# gyro_pcb.net
KiCad netlist of a schematic drawn in EAGLE
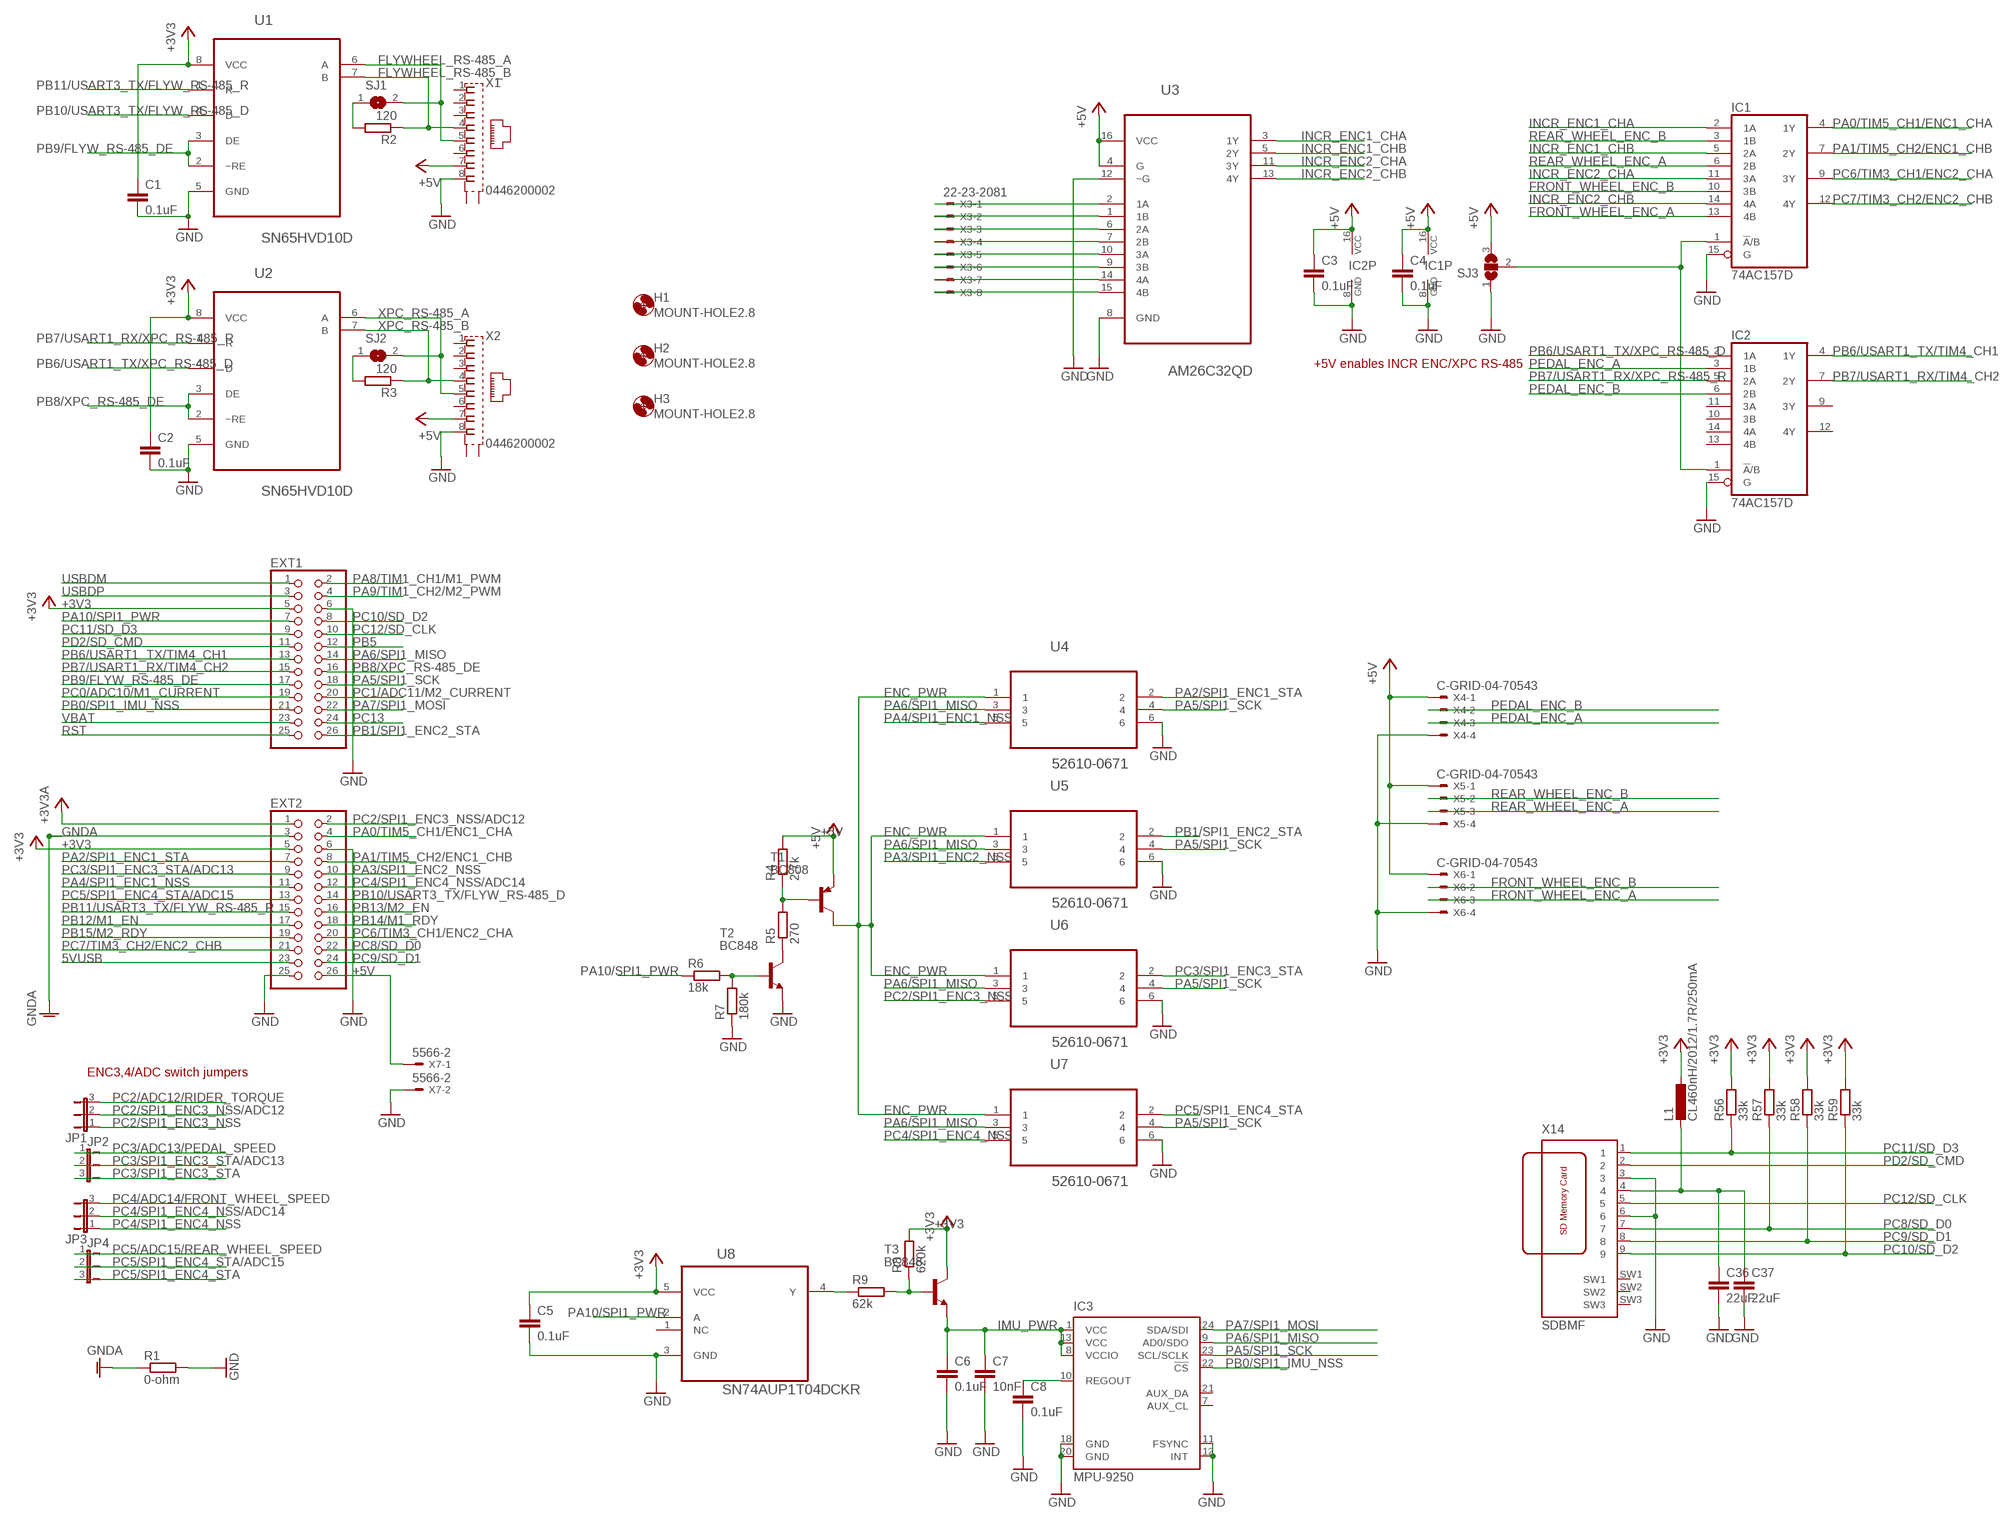
[diagram p0: schematic, sheet 1, part 1 of 2]
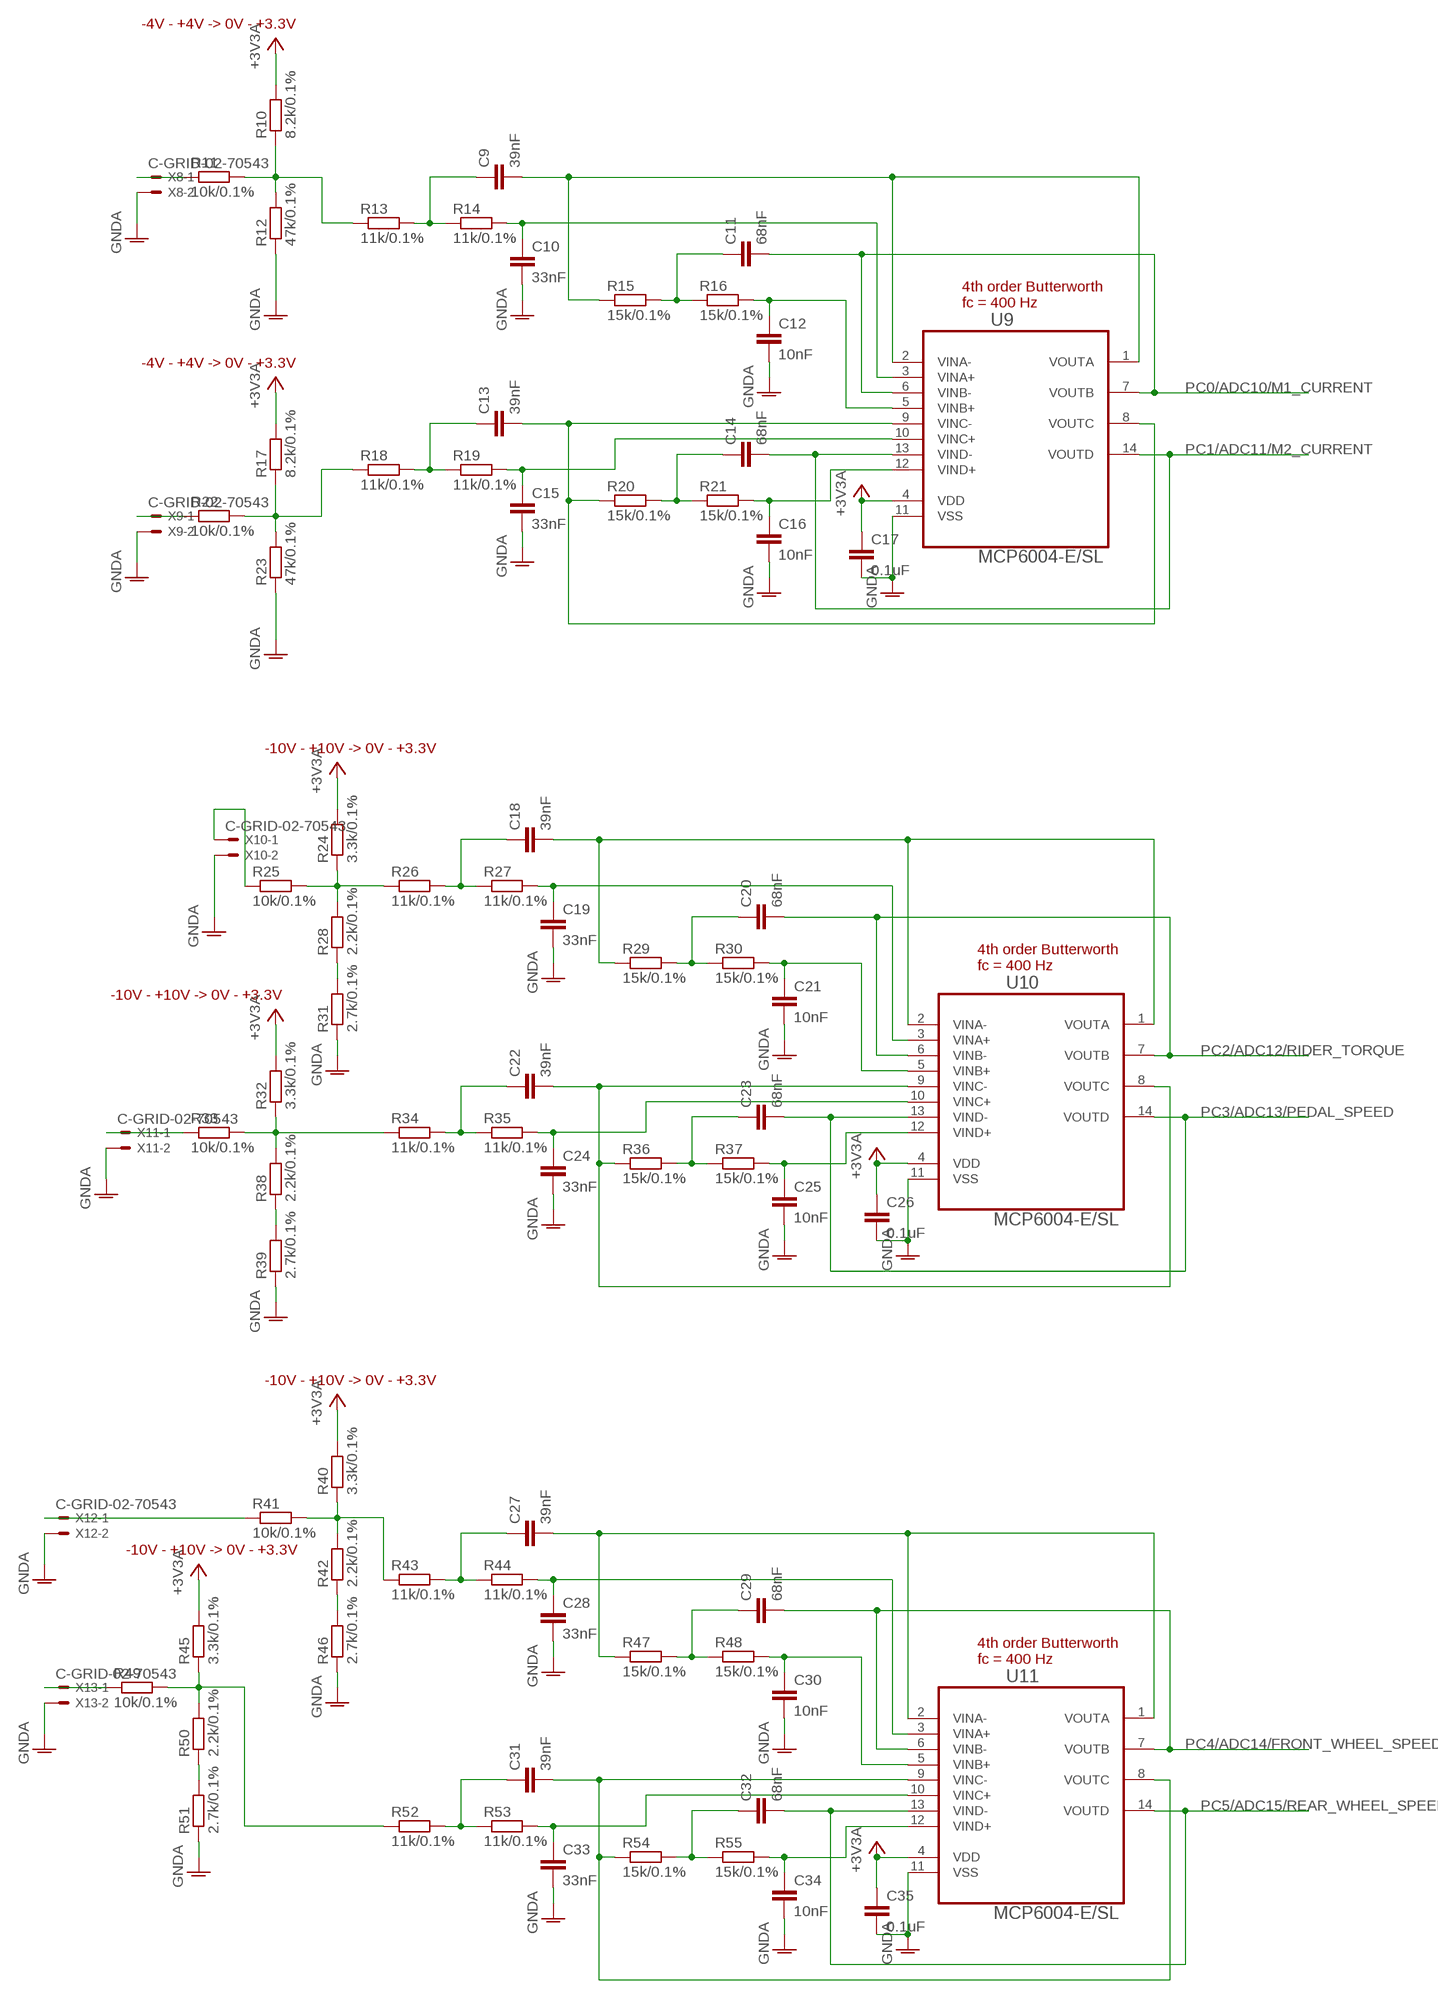
[diagram p1: schematic, sheet 1, part 2 of 2]

(export (version "E")
  (design (tool "Eeschema 10.0.6"))
  (components
    (comp (ref "C1")
      (value "0.1uF")
      (footprint "eagle-import:C0603")
      (libsource (lib "eagle-import") (part "C-EUC0603"))
    )
    (comp (ref "C2")
      (value "0.1uF")
      (footprint "eagle-import:C0603")
      (libsource (lib "eagle-import") (part "C-EUC0603"))
    )
    (comp (ref "C3")
      (value "0.1uF")
      (footprint "eagle-import:C0603")
      (libsource (lib "eagle-import") (part "C-EUC0603"))
    )
    (comp (ref "C4")
      (value "0.1uF")
      (footprint "eagle-import:C0603")
      (libsource (lib "eagle-import") (part "C-EUC0603"))
    )
    (comp (ref "C5")
      (value "0.1uF")
      (footprint "eagle-import:C0603")
      (libsource (lib "eagle-import") (part "C-EUC0603"))
    )
    (comp (ref "C6")
      (value "0.1uF")
      (footprint "eagle-import:C0603")
      (libsource (lib "eagle-import") (part "C-EUC0603"))
    )
    (comp (ref "C7")
      (value "10nF")
      (footprint "eagle-import:C0603")
      (libsource (lib "eagle-import") (part "C-EUC0603"))
    )
    (comp (ref "C8")
      (value "0.1uF")
      (footprint "eagle-import:C0603")
      (libsource (lib "eagle-import") (part "C-EUC0603"))
    )
    (comp (ref "C9")
      (value "39nF")
      (footprint "eagle-import:C0603")
      (libsource (lib "eagle-import") (part "C-EUC0603"))
    )
    (comp (ref "C10")
      (value "33nF")
      (footprint "eagle-import:C0603")
      (libsource (lib "eagle-import") (part "C-EUC0603"))
    )
    (comp (ref "C11")
      (value "68nF")
      (footprint "eagle-import:C0603")
      (libsource (lib "eagle-import") (part "C-EUC0603"))
    )
    (comp (ref "C12")
      (value "10nF")
      (footprint "eagle-import:C0603")
      (libsource (lib "eagle-import") (part "C-EUC0603"))
    )
    (comp (ref "C13")
      (value "39nF")
      (footprint "eagle-import:C0603")
      (libsource (lib "eagle-import") (part "C-EUC0603"))
    )
    (comp (ref "C14")
      (value "68nF")
      (footprint "eagle-import:C0603")
      (libsource (lib "eagle-import") (part "C-EUC0603"))
    )
    (comp (ref "C15")
      (value "33nF")
      (footprint "eagle-import:C0603")
      (libsource (lib "eagle-import") (part "C-EUC0603"))
    )
    (comp (ref "C16")
      (value "10nF")
      (footprint "eagle-import:C0603")
      (libsource (lib "eagle-import") (part "C-EUC0603"))
    )
    (comp (ref "C17")
      (value "0.1uF")
      (footprint "eagle-import:C0603")
      (libsource (lib "eagle-import") (part "C-EUC0603"))
    )
    (comp (ref "C18")
      (value "39nF")
      (footprint "eagle-import:C0603")
      (libsource (lib "eagle-import") (part "C-EUC0603"))
    )
    (comp (ref "C19")
      (value "33nF")
      (footprint "eagle-import:C0603")
      (libsource (lib "eagle-import") (part "C-EUC0603"))
    )
    (comp (ref "C20")
      (value "68nF")
      (footprint "eagle-import:C0603")
      (libsource (lib "eagle-import") (part "C-EUC0603"))
    )
    (comp (ref "C21")
      (value "10nF")
      (footprint "eagle-import:C0603")
      (libsource (lib "eagle-import") (part "C-EUC0603"))
    )
    (comp (ref "C22")
      (value "39nF")
      (footprint "eagle-import:C0603")
      (libsource (lib "eagle-import") (part "C-EUC0603"))
    )
    (comp (ref "C23")
      (value "68nF")
      (footprint "eagle-import:C0603")
      (libsource (lib "eagle-import") (part "C-EUC0603"))
    )
    (comp (ref "C24")
      (value "33nF")
      (footprint "eagle-import:C0603")
      (libsource (lib "eagle-import") (part "C-EUC0603"))
    )
    (comp (ref "C25")
      (value "10nF")
      (footprint "eagle-import:C0603")
      (libsource (lib "eagle-import") (part "C-EUC0603"))
    )
    (comp (ref "C26")
      (value "0.1uF")
      (footprint "eagle-import:C0603")
      (libsource (lib "eagle-import") (part "C-EUC0603"))
    )
    (comp (ref "C27")
      (value "39nF")
      (footprint "eagle-import:C0603")
      (libsource (lib "eagle-import") (part "C-EUC0603"))
    )
    (comp (ref "C28")
      (value "33nF")
      (footprint "eagle-import:C0603")
      (libsource (lib "eagle-import") (part "C-EUC0603"))
    )
    (comp (ref "C29")
      (value "68nF")
      (footprint "eagle-import:C0603")
      (libsource (lib "eagle-import") (part "C-EUC0603"))
    )
    (comp (ref "C30")
      (value "10nF")
      (footprint "eagle-import:C0603")
      (libsource (lib "eagle-import") (part "C-EUC0603"))
    )
    (comp (ref "C31")
      (value "39nF")
      (footprint "eagle-import:C0603")
      (libsource (lib "eagle-import") (part "C-EUC0603"))
    )
    (comp (ref "C32")
      (value "68nF")
      (footprint "eagle-import:C0603")
      (libsource (lib "eagle-import") (part "C-EUC0603"))
    )
    (comp (ref "C33")
      (value "33nF")
      (footprint "eagle-import:C0603")
      (libsource (lib "eagle-import") (part "C-EUC0603"))
    )
    (comp (ref "C34")
      (value "10nF")
      (footprint "eagle-import:C0603")
      (libsource (lib "eagle-import") (part "C-EUC0603"))
    )
    (comp (ref "C35")
      (value "0.1uF")
      (footprint "eagle-import:C0603")
      (libsource (lib "eagle-import") (part "C-EUC0603"))
    )
    (comp (ref "C36")
      (value "22uF")
      (footprint "eagle-import:C0603")
      (libsource (lib "eagle-import") (part "C-EUC0603"))
    )
    (comp (ref "C37")
      (value "22uF")
      (footprint "eagle-import:C0603")
      (libsource (lib "eagle-import") (part "C-EUC0603"))
    )
    (comp (ref "EXT1")
      (value "PINHD-2X13")
      (footprint "eagle-import:2X13")
      (libsource (lib "eagle-import") (part "PINHD-2X13"))
    )
    (comp (ref "EXT2")
      (value "PINHD-2X13")
      (footprint "eagle-import:2X13")
      (libsource (lib "eagle-import") (part "PINHD-2X13"))
    )
    (comp (ref "H1")
      (value "MOUNT-HOLE2.8")
      (footprint "eagle-import:2,8")
      (libsource (lib "eagle-import") (part "MOUNT-HOLE2.8"))
    )
    (comp (ref "H2")
      (value "MOUNT-HOLE2.8")
      (footprint "eagle-import:2,8")
      (libsource (lib "eagle-import") (part "MOUNT-HOLE2.8"))
    )
    (comp (ref "H3")
      (value "MOUNT-HOLE2.8")
      (footprint "eagle-import:2,8")
      (libsource (lib "eagle-import") (part "MOUNT-HOLE2.8"))
    )
    (comp (ref "IC1")
      (value "74AC157D")
      (footprint "eagle-import:SO16")
      (libsource (lib "eagle-import") (part "74157DAC"))
    )
    (comp (ref "IC2")
      (value "74AC157D")
      (footprint "eagle-import:SO16")
      (libsource (lib "eagle-import") (part "74157DAC"))
    )
    (comp (ref "IC3")
      (value "MPU-9250")
      (footprint "eagle-import:QFN24-SMALL")
      (libsource (lib "eagle-import") (part "MPU-9250"))
    )
    (comp (ref "JP1")
      (value "JP2E")
      (footprint "eagle-import:JP2")
      (libsource (lib "eagle-import") (part "JP2E"))
    )
    (comp (ref "JP2")
      (value "JP2E")
      (footprint "eagle-import:JP2")
      (libsource (lib "eagle-import") (part "JP2E"))
    )
    (comp (ref "JP3")
      (value "JP2E")
      (footprint "eagle-import:JP2")
      (libsource (lib "eagle-import") (part "JP2E"))
    )
    (comp (ref "JP4")
      (value "JP2E")
      (footprint "eagle-import:JP2")
      (libsource (lib "eagle-import") (part "JP2E"))
    )
    (comp (ref "L1")
      (value "CL460nH/2012/1.7R/250mA")
      (footprint "eagle-import:L2825P")
      (libsource (lib "eagle-import") (part "L-EUL2825P"))
    )
    (comp (ref "R1")
      (value "0-ohm")
      (footprint "eagle-import:R1218")
      (libsource (lib "eagle-import") (part "R-EU_R1218"))
    )
    (comp (ref "R2")
      (value "120")
      (footprint "eagle-import:R0603")
      (libsource (lib "eagle-import") (part "R-EU_R0603"))
    )
    (comp (ref "R3")
      (value "120")
      (footprint "eagle-import:R0603")
      (libsource (lib "eagle-import") (part "R-EU_R0603"))
    )
    (comp (ref "R4")
      (value "2.7k")
      (footprint "eagle-import:R1210")
      (libsource (lib "eagle-import") (part "R-EU_R1210"))
    )
    (comp (ref "R5")
      (value "270")
      (footprint "eagle-import:R1210")
      (libsource (lib "eagle-import") (part "R-EU_R1210"))
    )
    (comp (ref "R6")
      (value "18k")
      (footprint "eagle-import:R0603")
      (libsource (lib "eagle-import") (part "R-EU_R0603"))
    )
    (comp (ref "R7")
      (value "180k")
      (footprint "eagle-import:R0603")
      (libsource (lib "eagle-import") (part "R-EU_R0603"))
    )
    (comp (ref "R8")
      (value "620k")
      (footprint "eagle-import:R0603")
      (libsource (lib "eagle-import") (part "R-EU_R0603"))
    )
    (comp (ref "R9")
      (value "62k")
      (footprint "eagle-import:R0603")
      (libsource (lib "eagle-import") (part "R-EU_R0603"))
    )
    (comp (ref "R10")
      (value "8.2k/0.1%")
      (footprint "eagle-import:R0603")
      (libsource (lib "eagle-import") (part "R-EU_R0603"))
    )
    (comp (ref "R11")
      (value "10k/0.1%")
      (footprint "eagle-import:R0603")
      (libsource (lib "eagle-import") (part "R-EU_R0603"))
    )
    (comp (ref "R12")
      (value "47k/0.1%")
      (footprint "eagle-import:R0603")
      (libsource (lib "eagle-import") (part "R-EU_R0603"))
    )
    (comp (ref "R13")
      (value "11k/0.1%")
      (footprint "eagle-import:R0603")
      (libsource (lib "eagle-import") (part "R-EU_R0603"))
    )
    (comp (ref "R14")
      (value "11k/0.1%")
      (footprint "eagle-import:R0603")
      (libsource (lib "eagle-import") (part "R-EU_R0603"))
    )
    (comp (ref "R15")
      (value "15k/0.1%")
      (footprint "eagle-import:R0603")
      (libsource (lib "eagle-import") (part "R-EU_R0603"))
    )
    (comp (ref "R16")
      (value "15k/0.1%")
      (footprint "eagle-import:R0603")
      (libsource (lib "eagle-import") (part "R-EU_R0603"))
    )
    (comp (ref "R17")
      (value "8.2k/0.1%")
      (footprint "eagle-import:R0603")
      (libsource (lib "eagle-import") (part "R-EU_R0603"))
    )
    (comp (ref "R18")
      (value "11k/0.1%")
      (footprint "eagle-import:R0603")
      (libsource (lib "eagle-import") (part "R-EU_R0603"))
    )
    (comp (ref "R19")
      (value "11k/0.1%")
      (footprint "eagle-import:R0603")
      (libsource (lib "eagle-import") (part "R-EU_R0603"))
    )
    (comp (ref "R20")
      (value "15k/0.1%")
      (footprint "eagle-import:R0603")
      (libsource (lib "eagle-import") (part "R-EU_R0603"))
    )
    (comp (ref "R21")
      (value "15k/0.1%")
      (footprint "eagle-import:R0603")
      (libsource (lib "eagle-import") (part "R-EU_R0603"))
    )
    (comp (ref "R22")
      (value "10k/0.1%")
      (footprint "eagle-import:R0603")
      (libsource (lib "eagle-import") (part "R-EU_R0603"))
    )
    (comp (ref "R23")
      (value "47k/0.1%")
      (footprint "eagle-import:R0603")
      (libsource (lib "eagle-import") (part "R-EU_R0603"))
    )
    (comp (ref "R24")
      (value "3.3k/0.1%")
      (footprint "eagle-import:R0603")
      (libsource (lib "eagle-import") (part "R-EU_R0603"))
    )
    (comp (ref "R25")
      (value "10k/0.1%")
      (footprint "eagle-import:R0603")
      (libsource (lib "eagle-import") (part "R-EU_R0603"))
    )
    (comp (ref "R26")
      (value "11k/0.1%")
      (footprint "eagle-import:R0603")
      (libsource (lib "eagle-import") (part "R-EU_R0603"))
    )
    (comp (ref "R27")
      (value "11k/0.1%")
      (footprint "eagle-import:R0603")
      (libsource (lib "eagle-import") (part "R-EU_R0603"))
    )
    (comp (ref "R28")
      (value "2.2k/0.1%")
      (footprint "eagle-import:R0603")
      (libsource (lib "eagle-import") (part "R-EU_R0603"))
    )
    (comp (ref "R29")
      (value "15k/0.1%")
      (footprint "eagle-import:R0603")
      (libsource (lib "eagle-import") (part "R-EU_R0603"))
    )
    (comp (ref "R30")
      (value "15k/0.1%")
      (footprint "eagle-import:R0603")
      (libsource (lib "eagle-import") (part "R-EU_R0603"))
    )
    (comp (ref "R31")
      (value "2.7k/0.1%")
      (footprint "eagle-import:R0603")
      (libsource (lib "eagle-import") (part "R-EU_R0603"))
    )
    (comp (ref "R32")
      (value "3.3k/0.1%")
      (footprint "eagle-import:R0603")
      (libsource (lib "eagle-import") (part "R-EU_R0603"))
    )
    (comp (ref "R33")
      (value "10k/0.1%")
      (footprint "eagle-import:R0603")
      (libsource (lib "eagle-import") (part "R-EU_R0603"))
    )
    (comp (ref "R34")
      (value "11k/0.1%")
      (footprint "eagle-import:R0603")
      (libsource (lib "eagle-import") (part "R-EU_R0603"))
    )
    (comp (ref "R35")
      (value "11k/0.1%")
      (footprint "eagle-import:R0603")
      (libsource (lib "eagle-import") (part "R-EU_R0603"))
    )
    (comp (ref "R36")
      (value "15k/0.1%")
      (footprint "eagle-import:R0603")
      (libsource (lib "eagle-import") (part "R-EU_R0603"))
    )
    (comp (ref "R37")
      (value "15k/0.1%")
      (footprint "eagle-import:R0603")
      (libsource (lib "eagle-import") (part "R-EU_R0603"))
    )
    (comp (ref "R38")
      (value "2.2k/0.1%")
      (footprint "eagle-import:R0603")
      (libsource (lib "eagle-import") (part "R-EU_R0603"))
    )
    (comp (ref "R39")
      (value "2.7k/0.1%")
      (footprint "eagle-import:R0603")
      (libsource (lib "eagle-import") (part "R-EU_R0603"))
    )
    (comp (ref "R40")
      (value "3.3k/0.1%")
      (footprint "eagle-import:R0603")
      (libsource (lib "eagle-import") (part "R-EU_R0603"))
    )
    (comp (ref "R41")
      (value "10k/0.1%")
      (footprint "eagle-import:R0603")
      (libsource (lib "eagle-import") (part "R-EU_R0603"))
    )
    (comp (ref "R42")
      (value "2.2k/0.1%")
      (footprint "eagle-import:R0603")
      (libsource (lib "eagle-import") (part "R-EU_R0603"))
    )
    (comp (ref "R43")
      (value "11k/0.1%")
      (footprint "eagle-import:R0603")
      (libsource (lib "eagle-import") (part "R-EU_R0603"))
    )
    (comp (ref "R44")
      (value "11k/0.1%")
      (footprint "eagle-import:R0603")
      (libsource (lib "eagle-import") (part "R-EU_R0603"))
    )
    (comp (ref "R45")
      (value "3.3k/0.1%")
      (footprint "eagle-import:R0603")
      (libsource (lib "eagle-import") (part "R-EU_R0603"))
    )
    (comp (ref "R46")
      (value "2.7k/0.1%")
      (footprint "eagle-import:R0603")
      (libsource (lib "eagle-import") (part "R-EU_R0603"))
    )
    (comp (ref "R47")
      (value "15k/0.1%")
      (footprint "eagle-import:R0603")
      (libsource (lib "eagle-import") (part "R-EU_R0603"))
    )
    (comp (ref "R48")
      (value "15k/0.1%")
      (footprint "eagle-import:R0603")
      (libsource (lib "eagle-import") (part "R-EU_R0603"))
    )
    (comp (ref "R49")
      (value "10k/0.1%")
      (footprint "eagle-import:R0603")
      (libsource (lib "eagle-import") (part "R-EU_R0603"))
    )
    (comp (ref "R50")
      (value "2.2k/0.1%")
      (footprint "eagle-import:R0603")
      (libsource (lib "eagle-import") (part "R-EU_R0603"))
    )
    (comp (ref "R51")
      (value "2.7k/0.1%")
      (footprint "eagle-import:R0603")
      (libsource (lib "eagle-import") (part "R-EU_R0603"))
    )
    (comp (ref "R52")
      (value "11k/0.1%")
      (footprint "eagle-import:R0603")
      (libsource (lib "eagle-import") (part "R-EU_R0603"))
    )
    (comp (ref "R53")
      (value "11k/0.1%")
      (footprint "eagle-import:R0603")
      (libsource (lib "eagle-import") (part "R-EU_R0603"))
    )
    (comp (ref "R54")
      (value "15k/0.1%")
      (footprint "eagle-import:R0603")
      (libsource (lib "eagle-import") (part "R-EU_R0603"))
    )
    (comp (ref "R55")
      (value "15k/0.1%")
      (footprint "eagle-import:R0603")
      (libsource (lib "eagle-import") (part "R-EU_R0603"))
    )
    (comp (ref "R56")
      (value "33k")
      (footprint "eagle-import:R0603")
      (libsource (lib "eagle-import") (part "R-EU_R0603"))
    )
    (comp (ref "R57")
      (value "33k")
      (footprint "eagle-import:R0603")
      (libsource (lib "eagle-import") (part "R-EU_R0603"))
    )
    (comp (ref "R58")
      (value "33k")
      (footprint "eagle-import:R0603")
      (libsource (lib "eagle-import") (part "R-EU_R0603"))
    )
    (comp (ref "R59")
      (value "33k")
      (footprint "eagle-import:R0603")
      (libsource (lib "eagle-import") (part "R-EU_R0603"))
    )
    (comp (ref "SJ1") (value "SJ") (footprint "eagle-import:SJ") (libsource (lib "eagle-import") (part "SJ")))
    (comp (ref "SJ2") (value "SJ") (footprint "eagle-import:SJ") (libsource (lib "eagle-import") (part "SJ")))
    (comp (ref "SJ3")
      (value "SJ2W")
      (footprint "eagle-import:SJ_2")
      (libsource (lib "eagle-import") (part "SJ2W"))
    )
    (comp (ref "T1")
      (value "BC808")
      (footprint "eagle-import:SOT23-BEC")
      (libsource (lib "eagle-import") (part "-PNP-SOT23-BECBC808-16"))
    )
    (comp (ref "T2")
      (value "BC848")
      (footprint "eagle-import:SOT23")
      (libsource (lib "eagle-import") (part "BC848"))
    )
    (comp (ref "T3")
      (value "BC848")
      (footprint "eagle-import:SOT23")
      (libsource (lib "eagle-import") (part "BC848"))
    )
    (comp (ref "U1")
      (value "SN65HVD10D")
      (footprint "eagle-import:SOIC127P600X175-8N")
      (libsource (lib "eagle-import") (part "SN65HVD10D"))
    )
    (comp (ref "U2")
      (value "SN65HVD10D")
      (footprint "eagle-import:SOIC127P600X175-8N")
      (libsource (lib "eagle-import") (part "SN65HVD10D"))
    )
    (comp (ref "U3")
      (value "AM26C32QD")
      (footprint "eagle-import:SOIC127P600X175-16N")
      (libsource (lib "eagle-import") (part "AM26C32QD"))
    )
    (comp (ref "U4")
      (value "52610-0671")
      (footprint "eagle-import:MOLEX_52610-0671")
      (libsource (lib "eagle-import") (part "52610-0671"))
    )
    (comp (ref "U5")
      (value "52610-0671")
      (footprint "eagle-import:MOLEX_52610-0671")
      (libsource (lib "eagle-import") (part "52610-0671"))
    )
    (comp (ref "U6")
      (value "52610-0671")
      (footprint "eagle-import:MOLEX_52610-0671")
      (libsource (lib "eagle-import") (part "52610-0671"))
    )
    (comp (ref "U7")
      (value "52610-0671")
      (footprint "eagle-import:MOLEX_52610-0671")
      (libsource (lib "eagle-import") (part "52610-0671"))
    )
    (comp (ref "U8")
      (value "SN74AUP1T04DCKR")
      (footprint "eagle-import:SOT65P210X110-5N")
      (libsource (lib "eagle-import") (part "SN74AUP1T04DCKR"))
    )
    (comp (ref "U9")
      (value "MCP6004-E/SL")
      (footprint "eagle-import:SOIC127P600X175-14N")
      (libsource (lib "eagle-import") (part "MCP6004-E/SL"))
    )
    (comp (ref "U10")
      (value "MCP6004-E/SL")
      (footprint "eagle-import:SOIC127P600X175-14N")
      (libsource (lib "eagle-import") (part "MCP6004-E/SL"))
    )
    (comp (ref "U11")
      (value "MCP6004-E/SL")
      (footprint "eagle-import:SOIC127P600X175-14N")
      (libsource (lib "eagle-import") (part "MCP6004-E/SL"))
    )
    (comp (ref "X1")
      (value "0446200002")
      (footprint "eagle-import:0446200002")
      (fields (field (name "MF") "MOLEX"))
      (libsource (lib "eagle-import") (part "0446200002"))
    )
    (comp (ref "X2")
      (value "0446200002")
      (footprint "eagle-import:0446200002")
      (fields (field (name "MF") "MOLEX"))
      (libsource (lib "eagle-import") (part "0446200002"))
    )
    (comp (ref "X3")
      (value "22-23-2081")
      (footprint "eagle-import:22-23-2081")
      (fields (field (name "MF") "MOLEX"))
      (libsource (lib "eagle-import") (part "22-23-2081"))
    )
    (comp (ref "X4")
      (value "C-GRID-04-70543")
      (footprint "eagle-import:70543-04")
      (libsource (lib "eagle-import") (part "C-GRID-04-70543"))
    )
    (comp (ref "X5")
      (value "C-GRID-04-70543")
      (footprint "eagle-import:70543-04")
      (libsource (lib "eagle-import") (part "C-GRID-04-70543"))
    )
    (comp (ref "X6")
      (value "C-GRID-04-70543")
      (footprint "eagle-import:70543-04")
      (libsource (lib "eagle-import") (part "C-GRID-04-70543"))
    )
    (comp (ref "X7")
      (value "5566-2")
      (footprint "eagle-import:5566-2")
      (libsource (lib "eagle-import") (part "5566-2"))
    )
    (comp (ref "X8")
      (value "C-GRID-02-70543")
      (footprint "eagle-import:70543-02")
      (libsource (lib "eagle-import") (part "C-GRID-02-70543"))
    )
    (comp (ref "X9")
      (value "C-GRID-02-70543")
      (footprint "eagle-import:70543-02")
      (libsource (lib "eagle-import") (part "C-GRID-02-70543"))
    )
    (comp (ref "X10")
      (value "C-GRID-02-70543")
      (footprint "eagle-import:70543-02")
      (libsource (lib "eagle-import") (part "C-GRID-02-70543"))
    )
    (comp (ref "X11")
      (value "C-GRID-02-70543")
      (footprint "eagle-import:70543-02")
      (libsource (lib "eagle-import") (part "C-GRID-02-70543"))
    )
    (comp (ref "X12")
      (value "C-GRID-02-70543")
      (footprint "eagle-import:70543-02")
      (libsource (lib "eagle-import") (part "C-GRID-02-70543"))
    )
    (comp (ref "X13")
      (value "C-GRID-02-70543")
      (footprint "eagle-import:70543-02")
      (libsource (lib "eagle-import") (part "C-GRID-02-70543"))
    )
    (comp (ref "X14")
      (value "SDBMF")
      (footprint "eagle-import:SDBMF-009XXBXX2")
      (libsource (lib "eagle-import") (part "SDBMF"))
    )
  )
  (nets
    (net (code "1") (name "+3V3") (class "Default")
      (node (ref "C1") (pin "1") (pinfunction "1_1") (pintype "passive"))
      (node (ref "C2") (pin "1") (pinfunction "1_1") (pintype "passive"))
      (node (ref "C5") (pin "1") (pinfunction "1_1") (pintype "passive"))
      (node (ref "EXT1") (pin "5") (pinfunction "5_5") (pintype "passive"))
      (node (ref "EXT2") (pin "5") (pinfunction "5_5") (pintype "passive"))
      (node (ref "L1") (pin "1") (pinfunction "1_1") (pintype "passive"))
      (node (ref "R56") (pin "2") (pinfunction "2_2") (pintype "passive"))
      (node (ref "R57") (pin "2") (pinfunction "2_2") (pintype "passive"))
      (node (ref "R58") (pin "2") (pinfunction "2_2") (pintype "passive"))
      (node (ref "R59") (pin "2") (pinfunction "2_2") (pintype "passive"))
      (node (ref "R8") (pin "2") (pinfunction "2_2") (pintype "passive"))
      (node (ref "T3") (pin "3") (pinfunction "C_3") (pintype "passive"))
      (node (ref "U1") (pin "8") (pinfunction "VCC_8") (pintype "power_in"))
      (node (ref "U2") (pin "8") (pinfunction "VCC_8") (pintype "power_in"))
      (node (ref "U8") (pin "5") (pinfunction "VCC_5") (pintype "power_in"))
    )
    (net (code "2") (name "+3V3A") (class "Default")
      (node (ref "C17") (pin "1") (pinfunction "1_1") (pintype "passive"))
      (node (ref "C26") (pin "1") (pinfunction "1_1") (pintype "passive"))
      (node (ref "C35") (pin "1") (pinfunction "1_1") (pintype "passive"))
      (node (ref "EXT2") (pin "1") (pinfunction "1_1") (pintype "passive"))
      (node (ref "R10") (pin "2") (pinfunction "2_2") (pintype "passive"))
      (node (ref "R17") (pin "2") (pinfunction "2_2") (pintype "passive"))
      (node (ref "R24") (pin "2") (pinfunction "2_2") (pintype "passive"))
      (node (ref "R32") (pin "2") (pinfunction "2_2") (pintype "passive"))
      (node (ref "R40") (pin "2") (pinfunction "2_2") (pintype "passive"))
      (node (ref "R45") (pin "2") (pinfunction "2_2") (pintype "passive"))
      (node (ref "U10") (pin "4") (pinfunction "VDD_4") (pintype "power_in"))
      (node (ref "U11") (pin "4") (pinfunction "VDD_4") (pintype "power_in"))
      (node (ref "U9") (pin "4") (pinfunction "VDD_4") (pintype "power_in"))
    )
    (net (code "3") (name "+5V") (class "Default")
      (node (ref "C3") (pin "1") (pinfunction "1_1") (pintype "passive"))
      (node (ref "C4") (pin "1") (pinfunction "1_1") (pintype "passive"))
      (node (ref "EXT2") (pin "26") (pinfunction "26_26") (pintype "passive"))
      (node (ref "IC1") (pin "16") (pinfunction "VCC_16") (pintype "power_in"))
      (node (ref "IC2") (pin "16") (pinfunction "VCC_16") (pintype "power_in"))
      (node (ref "R4") (pin "2") (pinfunction "2_2") (pintype "passive"))
      (node (ref "SJ3") (pin "3") (pinfunction "3_3") (pintype "passive"))
      (node (ref "T1") (pin "E") (pinfunction "E_E") (pintype "passive"))
      (node (ref "U3") (pin "16") (pinfunction "VCC_16") (pintype "power_in"))
      (node (ref "U3") (pin "4") (pinfunction "G_4") (pintype "input"))
      (node (ref "X1") (pin "7") (pinfunction "7_7") (pintype "passive"))
      (node (ref "X2") (pin "7") (pinfunction "7_7") (pintype "passive"))
      (node (ref "X4") (pin "1") (pinfunction "S_1") (pintype "passive"))
      (node (ref "X5") (pin "1") (pinfunction "S_1") (pintype "passive"))
      (node (ref "X6") (pin "1") (pinfunction "S_1") (pintype "passive"))
      (node (ref "X7") (pin "1") (pinfunction "S_1") (pintype "passive"))
    )
    (net (code "4") (name "/5VUSB") (class "Default")
      (node (ref "EXT2") (pin "23") (pinfunction "23_23") (pintype "passive"))
    )
    (net (code "5") (name "/ENC_PWR") (class "Default")
      (node (ref "T1") (pin "C") (pinfunction "C_C") (pintype "passive"))
      (node (ref "U4") (pin "1") (pinfunction "1_1") (pintype "passive"))
      (node (ref "U5") (pin "1") (pinfunction "1_1") (pintype "passive"))
      (node (ref "U6") (pin "1") (pinfunction "1_1") (pintype "passive"))
      (node (ref "U7") (pin "1") (pinfunction "1_1") (pintype "passive"))
    )
    (net (code "6") (name "/FLYWHEEL_RS-485_A") (class "Default")
      (node (ref "SJ1") (pin "2") (pinfunction "2_2") (pintype "passive"))
      (node (ref "U1") (pin "6") (pinfunction "A_6") (pintype "output"))
      (node (ref "X1") (pin "5") (pinfunction "5_5") (pintype "passive"))
    )
    (net (code "7") (name "/FLYWHEEL_RS-485_B") (class "Default")
      (node (ref "R2") (pin "1") (pinfunction "1_1") (pintype "passive"))
      (node (ref "U1") (pin "7") (pinfunction "B_7") (pintype "output"))
      (node (ref "X1") (pin "4") (pinfunction "4_4") (pintype "passive"))
    )
    (net (code "8") (name "/FRONT_WHEEL_ENC_A") (class "Default")
      (node (ref "IC1") (pin "13") (pinfunction "4B_13") (pintype "input"))
      (node (ref "X6") (pin "3") (pinfunction "S_3") (pintype "passive"))
    )
    (net (code "9") (name "/FRONT_WHEEL_ENC_B") (class "Default")
      (node (ref "IC1") (pin "10") (pinfunction "3B_10") (pintype "input"))
      (node (ref "X6") (pin "2") (pinfunction "S_2") (pintype "passive"))
    )
    (net (code "10") (name "/IMU_PWR") (class "Default")
      (node (ref "C6") (pin "1") (pinfunction "1_1") (pintype "passive"))
      (node (ref "C7") (pin "1") (pinfunction "1_1") (pintype "passive"))
      (node (ref "IC3") (pin "1") (pinfunction "VCC_1") (pintype "power_in"))
      (node (ref "IC3") (pin "13") (pinfunction "VCC_13") (pintype "power_in"))
      (node (ref "IC3") (pin "8") (pinfunction "VCCIO_8") (pintype "power_in"))
      (node (ref "T3") (pin "2") (pinfunction "E_2") (pintype "passive"))
    )
    (net (code "11") (name "/INCR_ENC1_CHA") (class "Default")
      (node (ref "IC1") (pin "2") (pinfunction "1A_2") (pintype "input"))
      (node (ref "U3") (pin "3") (pinfunction "1Y_3") (pintype "output"))
    )
    (net (code "12") (name "/INCR_ENC1_CHB") (class "Default")
      (node (ref "IC1") (pin "5") (pinfunction "2A_5") (pintype "input"))
      (node (ref "U3") (pin "5") (pinfunction "2Y_5") (pintype "output"))
    )
    (net (code "13") (name "/INCR_ENC2_CHA") (class "Default")
      (node (ref "IC1") (pin "11") (pinfunction "3A_11") (pintype "input"))
      (node (ref "U3") (pin "11") (pinfunction "3Y_11") (pintype "output"))
    )
    (net (code "14") (name "/INCR_ENC2_CHB") (class "Default")
      (node (ref "IC1") (pin "14") (pinfunction "4A_14") (pintype "input"))
      (node (ref "U3") (pin "13") (pinfunction "4Y_13") (pintype "output"))
    )
    (net (code "15") (name "/PA0{slash}TIM5_CH1{slash}ENC1_CHA") (class "Default")
      (node (ref "EXT2") (pin "4") (pinfunction "4_4") (pintype "passive"))
      (node (ref "IC1") (pin "4") (pinfunction "1Y_4") (pintype "output"))
    )
    (net (code "16") (name "/PA1{slash}TIM5_CH2{slash}ENC1_CHB") (class "Default")
      (node (ref "EXT2") (pin "8") (pinfunction "8_8") (pintype "passive"))
      (node (ref "IC1") (pin "7") (pinfunction "2Y_7") (pintype "output"))
    )
    (net (code "17") (name "/PA2{slash}SPI1_ENC1_STA") (class "Default")
      (node (ref "EXT2") (pin "7") (pinfunction "7_7") (pintype "passive"))
      (node (ref "U4") (pin "2") (pinfunction "2_2") (pintype "passive"))
    )
    (net (code "18") (name "/PA3{slash}SPI1_ENC2_NSS") (class "Default")
      (node (ref "EXT2") (pin "10") (pinfunction "10_10") (pintype "passive"))
      (node (ref "U5") (pin "5") (pinfunction "5_5") (pintype "passive"))
    )
    (net (code "19") (name "/PA4{slash}SPI1_ENC1_NSS") (class "Default")
      (node (ref "EXT2") (pin "11") (pinfunction "11_11") (pintype "passive"))
      (node (ref "U4") (pin "5") (pinfunction "5_5") (pintype "passive"))
    )
    (net (code "20") (name "/PA5{slash}SPI1_SCK") (class "Default")
      (node (ref "EXT1") (pin "18") (pinfunction "18_18") (pintype "passive"))
      (node (ref "IC3") (pin "23") (pinfunction "SCL/SCLK_23") (pintype "bidirectional"))
      (node (ref "U4") (pin "4") (pinfunction "4_4") (pintype "passive"))
      (node (ref "U5") (pin "4") (pinfunction "4_4") (pintype "passive"))
      (node (ref "U6") (pin "4") (pinfunction "4_4") (pintype "passive"))
      (node (ref "U7") (pin "4") (pinfunction "4_4") (pintype "passive"))
    )
    (net (code "21") (name "/PA6{slash}SPI1_MISO") (class "Default")
      (node (ref "EXT1") (pin "14") (pinfunction "14_14") (pintype "passive"))
      (node (ref "IC3") (pin "9") (pinfunction "AD0/SDO_9") (pintype "input"))
      (node (ref "U4") (pin "3") (pinfunction "3_3") (pintype "passive"))
      (node (ref "U5") (pin "3") (pinfunction "3_3") (pintype "passive"))
      (node (ref "U6") (pin "3") (pinfunction "3_3") (pintype "passive"))
      (node (ref "U7") (pin "3") (pinfunction "3_3") (pintype "passive"))
    )
    (net (code "22") (name "/PA7{slash}SPI1_MOSI") (class "Default")
      (node (ref "EXT1") (pin "22") (pinfunction "22_22") (pintype "passive"))
      (node (ref "IC3") (pin "24") (pinfunction "SDA/SDI_24") (pintype "output"))
    )
    (net (code "23") (name "/PA8{slash}TIM1_CH1{slash}M1_PWM") (class "Default")
      (node (ref "EXT1") (pin "2") (pinfunction "2_2") (pintype "passive"))
    )
    (net (code "24") (name "/PA9{slash}TIM1_CH2{slash}M2_PWM") (class "Default")
      (node (ref "EXT1") (pin "4") (pinfunction "4_4") (pintype "passive"))
    )
    (net (code "25") (name "/PA10{slash}SPI1_PWR") (class "Default")
      (node (ref "EXT1") (pin "7") (pinfunction "7_7") (pintype "passive"))
      (node (ref "R6") (pin "1") (pinfunction "1_1") (pintype "passive"))
      (node (ref "U8") (pin "2") (pinfunction "A_2") (pintype "input"))
    )
    (net (code "26") (name "/PB0{slash}SPI1_IMU_NSS") (class "Default")
      (node (ref "EXT1") (pin "21") (pinfunction "21_21") (pintype "passive"))
      (node (ref "IC3") (pin "22") (pinfunction "~{CS}_22") (pintype "input"))
    )
    (net (code "27") (name "/PB1{slash}SPI1_ENC2_STA") (class "Default")
      (node (ref "EXT1") (pin "26") (pinfunction "26_26") (pintype "passive"))
      (node (ref "U5") (pin "2") (pinfunction "2_2") (pintype "passive"))
    )
    (net (code "28") (name "/PB5") (class "Default")
      (node (ref "EXT1") (pin "12") (pinfunction "12_12") (pintype "passive"))
    )
    (net (code "29") (name "/PB6{slash}USART1_TX{slash}TIM4_CH1") (class "Default")
      (node (ref "EXT1") (pin "13") (pinfunction "13_13") (pintype "passive"))
      (node (ref "IC2") (pin "4") (pinfunction "1Y_4") (pintype "output"))
    )
    (net (code "30") (name "/PB6{slash}USART1_TX{slash}XPC_RS-485_D") (class "Default")
      (node (ref "IC2") (pin "2") (pinfunction "1A_2") (pintype "input"))
      (node (ref "U2") (pin "4") (pinfunction "D_4") (pintype "input"))
    )
    (net (code "31") (name "/PB7{slash}USART1_RX{slash}TIM4_CH2") (class "Default")
      (node (ref "EXT1") (pin "15") (pinfunction "15_15") (pintype "passive"))
      (node (ref "IC2") (pin "7") (pinfunction "2Y_7") (pintype "output"))
    )
    (net (code "32") (name "/PB7{slash}USART1_RX{slash}XPC_RS-485_R") (class "Default")
      (node (ref "IC2") (pin "5") (pinfunction "2A_5") (pintype "input"))
      (node (ref "U2") (pin "1") (pinfunction "R_1") (pintype "input"))
    )
    (net (code "33") (name "/PB8{slash}XPC_RS-485_DE") (class "Default")
      (node (ref "EXT1") (pin "16") (pinfunction "16_16") (pintype "passive"))
      (node (ref "U2") (pin "2") (pinfunction "~{RE}_2") (pintype "input"))
      (node (ref "U2") (pin "3") (pinfunction "DE_3") (pintype "input"))
    )
    (net (code "34") (name "/PB9{slash}FLYW_RS-485_DE") (class "Default")
      (node (ref "EXT1") (pin "17") (pinfunction "17_17") (pintype "passive"))
      (node (ref "U1") (pin "2") (pinfunction "~{RE}_2") (pintype "input"))
      (node (ref "U1") (pin "3") (pinfunction "DE_3") (pintype "input"))
    )
    (net (code "35") (name "/PB10{slash}USART3_TX{slash}FLYW_RS-485_D") (class "Default")
      (node (ref "EXT2") (pin "14") (pinfunction "14_14") (pintype "passive"))
      (node (ref "U1") (pin "4") (pinfunction "D_4") (pintype "input"))
    )
    (net (code "36") (name "/PB11{slash}USART3_TX{slash}FLYW_RS-485_R") (class "Default")
      (node (ref "EXT2") (pin "15") (pinfunction "15_15") (pintype "passive"))
      (node (ref "U1") (pin "1") (pinfunction "R_1") (pintype "input"))
    )
    (net (code "37") (name "/PB12{slash}M1_EN") (class "Default")
      (node (ref "EXT2") (pin "17") (pinfunction "17_17") (pintype "passive"))
    )
    (net (code "38") (name "/PB13{slash}M2_EN") (class "Default")
      (node (ref "EXT2") (pin "16") (pinfunction "16_16") (pintype "passive"))
    )
    (net (code "39") (name "/PB14{slash}M1_RDY") (class "Default")
      (node (ref "EXT2") (pin "18") (pinfunction "18_18") (pintype "passive"))
    )
    (net (code "40") (name "/PB15{slash}M2_RDY") (class "Default")
      (node (ref "EXT2") (pin "19") (pinfunction "19_19") (pintype "passive"))
    )
    (net (code "41") (name "/PC0{slash}ADC10{slash}M1_CURRENT") (class "Default")
      (node (ref "C11") (pin "2") (pinfunction "2_2") (pintype "passive"))
      (node (ref "EXT1") (pin "19") (pinfunction "19_19") (pintype "passive"))
      (node (ref "U9") (pin "6") (pinfunction "VINB-_6") (pintype "input"))
      (node (ref "U9") (pin "7") (pinfunction "VOUTB_7") (pintype "output"))
    )
    (net (code "42") (name "/PC1{slash}ADC11{slash}M2_CURRENT") (class "Default")
      (node (ref "C14") (pin "2") (pinfunction "2_2") (pintype "passive"))
      (node (ref "EXT1") (pin "20") (pinfunction "20_20") (pintype "passive"))
      (node (ref "U9") (pin "13") (pinfunction "VIND-_13") (pintype "input"))
      (node (ref "U9") (pin "14") (pinfunction "VOUTD_14") (pintype "output"))
    )
    (net (code "43") (name "/PC2{slash}ADC12{slash}RIDER_TORQUE") (class "Default")
      (node (ref "C20") (pin "2") (pinfunction "2_2") (pintype "passive"))
      (node (ref "JP1") (pin "3") (pinfunction "3_3") (pintype "passive"))
      (node (ref "U10") (pin "6") (pinfunction "VINB-_6") (pintype "input"))
      (node (ref "U10") (pin "7") (pinfunction "VOUTB_7") (pintype "output"))
    )
    (net (code "44") (name "/PC2{slash}SPI1_ENC3_NSS") (class "Default")
      (node (ref "JP1") (pin "1") (pinfunction "1_1") (pintype "passive"))
      (node (ref "U6") (pin "5") (pinfunction "5_5") (pintype "passive"))
    )
    (net (code "45") (name "/PC2{slash}SPI1_ENC3_NSS{slash}ADC12") (class "Default")
      (node (ref "EXT2") (pin "2") (pinfunction "2_2") (pintype "passive"))
      (node (ref "JP1") (pin "2") (pinfunction "2_2") (pintype "passive"))
    )
    (net (code "46") (name "/PC3{slash}ADC13{slash}PEDAL_SPEED") (class "Default")
      (node (ref "C23") (pin "2") (pinfunction "2_2") (pintype "passive"))
      (node (ref "JP2") (pin "1") (pinfunction "1_1") (pintype "passive"))
      (node (ref "U10") (pin "13") (pinfunction "VIND-_13") (pintype "input"))
      (node (ref "U10") (pin "14") (pinfunction "VOUTD_14") (pintype "output"))
    )
    (net (code "47") (name "/PC3{slash}SPI1_ENC3_STA") (class "Default")
      (node (ref "JP2") (pin "3") (pinfunction "3_3") (pintype "passive"))
      (node (ref "U6") (pin "2") (pinfunction "2_2") (pintype "passive"))
    )
    (net (code "48") (name "/PC3{slash}SPI1_ENC3_STA{slash}ADC13") (class "Default")
      (node (ref "EXT2") (pin "9") (pinfunction "9_9") (pintype "passive"))
      (node (ref "JP2") (pin "2") (pinfunction "2_2") (pintype "passive"))
    )
    (net (code "49") (name "/PC4{slash}ADC14{slash}FRONT_WHEEL_SPEED") (class "Default")
      (node (ref "C29") (pin "2") (pinfunction "2_2") (pintype "passive"))
      (node (ref "JP3") (pin "3") (pinfunction "3_3") (pintype "passive"))
      (node (ref "U11") (pin "6") (pinfunction "VINB-_6") (pintype "input"))
      (node (ref "U11") (pin "7") (pinfunction "VOUTB_7") (pintype "output"))
    )
    (net (code "50") (name "/PC4{slash}SPI1_ENC4_NSS") (class "Default")
      (node (ref "JP3") (pin "1") (pinfunction "1_1") (pintype "passive"))
      (node (ref "U7") (pin "5") (pinfunction "5_5") (pintype "passive"))
    )
    (net (code "51") (name "/PC4{slash}SPI1_ENC4_NSS{slash}ADC14") (class "Default")
      (node (ref "EXT2") (pin "12") (pinfunction "12_12") (pintype "passive"))
      (node (ref "JP3") (pin "2") (pinfunction "2_2") (pintype "passive"))
    )
    (net (code "52") (name "/PC5{slash}ADC15{slash}REAR_WHEEL_SPEED") (class "Default")
      (node (ref "C32") (pin "2") (pinfunction "2_2") (pintype "passive"))
      (node (ref "JP4") (pin "1") (pinfunction "1_1") (pintype "passive"))
      (node (ref "U11") (pin "13") (pinfunction "VIND-_13") (pintype "input"))
      (node (ref "U11") (pin "14") (pinfunction "VOUTD_14") (pintype "output"))
    )
    (net (code "53") (name "/PC5{slash}SPI1_ENC4_STA") (class "Default")
      (node (ref "JP4") (pin "3") (pinfunction "3_3") (pintype "passive"))
      (node (ref "U7") (pin "2") (pinfunction "2_2") (pintype "passive"))
    )
    (net (code "54") (name "/PC5{slash}SPI1_ENC4_STA{slash}ADC15") (class "Default")
      (node (ref "EXT2") (pin "13") (pinfunction "13_13") (pintype "passive"))
      (node (ref "JP4") (pin "2") (pinfunction "2_2") (pintype "passive"))
    )
    (net (code "55") (name "/PC6{slash}TIM3_CH1{slash}ENC2_CHA") (class "Default")
      (node (ref "EXT2") (pin "20") (pinfunction "20_20") (pintype "passive"))
      (node (ref "IC1") (pin "9") (pinfunction "3Y_9") (pintype "output"))
    )
    (net (code "56") (name "/PC7{slash}TIM3_CH2{slash}ENC2_CHB") (class "Default")
      (node (ref "EXT2") (pin "21") (pinfunction "21_21") (pintype "passive"))
      (node (ref "IC1") (pin "12") (pinfunction "4Y_12") (pintype "output"))
    )
    (net (code "57") (name "/PC8{slash}SD_D0") (class "Default")
      (node (ref "EXT2") (pin "22") (pinfunction "22_22") (pintype "passive"))
      (node (ref "R57") (pin "1") (pinfunction "1_1") (pintype "passive"))
      (node (ref "X14") (pin "7") (pinfunction "7_7") (pintype "passive"))
    )
    (net (code "58") (name "/PC9{slash}SD_D1") (class "Default")
      (node (ref "EXT2") (pin "24") (pinfunction "24_24") (pintype "passive"))
      (node (ref "R58") (pin "1") (pinfunction "1_1") (pintype "passive"))
      (node (ref "X14") (pin "8") (pinfunction "8_8") (pintype "passive"))
    )
    (net (code "59") (name "/PC10{slash}SD_D2") (class "Default")
      (node (ref "EXT1") (pin "8") (pinfunction "8_8") (pintype "passive"))
      (node (ref "R59") (pin "1") (pinfunction "1_1") (pintype "passive"))
      (node (ref "X14") (pin "9") (pinfunction "9_9") (pintype "passive"))
    )
    (net (code "60") (name "/PC11{slash}SD_D3") (class "Default")
      (node (ref "EXT1") (pin "9") (pinfunction "9_9") (pintype "passive"))
      (node (ref "R56") (pin "1") (pinfunction "1_1") (pintype "passive"))
      (node (ref "X14") (pin "1") (pinfunction "1_1") (pintype "passive"))
    )
    (net (code "61") (name "/PC12{slash}SD_CLK") (class "Default")
      (node (ref "EXT1") (pin "10") (pinfunction "10_10") (pintype "passive"))
      (node (ref "X14") (pin "5") (pinfunction "5_5") (pintype "passive"))
    )
    (net (code "62") (name "/PC13") (class "Default")
      (node (ref "EXT1") (pin "24") (pinfunction "24_24") (pintype "passive"))
    )
    (net (code "63") (name "/PD2{slash}SD_CMD") (class "Default")
      (node (ref "EXT1") (pin "11") (pinfunction "11_11") (pintype "passive"))
      (node (ref "X14") (pin "2") (pinfunction "2_2") (pintype "passive"))
    )
    (net (code "64") (name "/PEDAL_ENC_A") (class "Default")
      (node (ref "IC2") (pin "3") (pinfunction "1B_3") (pintype "input"))
      (node (ref "X4") (pin "3") (pinfunction "S_3") (pintype "passive"))
    )
    (net (code "65") (name "/PEDAL_ENC_B") (class "Default")
      (node (ref "IC2") (pin "6") (pinfunction "2B_6") (pintype "input"))
      (node (ref "X4") (pin "2") (pinfunction "S_2") (pintype "passive"))
    )
    (net (code "66") (name "/REAR_WHEEL_ENC_A") (class "Default")
      (node (ref "IC1") (pin "6") (pinfunction "2B_6") (pintype "input"))
      (node (ref "X5") (pin "3") (pinfunction "S_3") (pintype "passive"))
    )
    (net (code "67") (name "/REAR_WHEEL_ENC_B") (class "Default")
      (node (ref "IC1") (pin "3") (pinfunction "1B_3") (pintype "input"))
      (node (ref "X5") (pin "2") (pinfunction "S_2") (pintype "passive"))
    )
    (net (code "68") (name "/RST") (class "Default")
      (node (ref "EXT1") (pin "25") (pinfunction "25_25") (pintype "passive"))
    )
    (net (code "69") (name "/USBDM") (class "Default")
      (node (ref "EXT1") (pin "1") (pinfunction "1_1") (pintype "passive"))
    )
    (net (code "70") (name "/USBDP") (class "Default")
      (node (ref "EXT1") (pin "3") (pinfunction "3_3") (pintype "passive"))
    )
    (net (code "71") (name "/VBAT") (class "Default")
      (node (ref "EXT1") (pin "23") (pinfunction "23_23") (pintype "passive"))
    )
    (net (code "72") (name "/XPC_RS-485_A") (class "Default")
      (node (ref "SJ2") (pin "2") (pinfunction "2_2") (pintype "passive"))
      (node (ref "U2") (pin "6") (pinfunction "A_6") (pintype "output"))
      (node (ref "X2") (pin "5") (pinfunction "5_5") (pintype "passive"))
    )
    (net (code "73") (name "/XPC_RS-485_B") (class "Default")
      (node (ref "R3") (pin "1") (pinfunction "1_1") (pintype "passive"))
      (node (ref "U2") (pin "7") (pinfunction "B_7") (pintype "output"))
      (node (ref "X2") (pin "4") (pinfunction "4_4") (pintype "passive"))
    )
    (net (code "74") (name "GND") (class "Default")
      (node (ref "C1") (pin "2") (pinfunction "2_2") (pintype "passive"))
      (node (ref "C2") (pin "2") (pinfunction "2_2") (pintype "passive"))
      (node (ref "C3") (pin "2") (pinfunction "2_2") (pintype "passive"))
      (node (ref "C36") (pin "2") (pinfunction "2_2") (pintype "passive"))
      (node (ref "C37") (pin "2") (pinfunction "2_2") (pintype "passive"))
      (node (ref "C4") (pin "2") (pinfunction "2_2") (pintype "passive"))
      (node (ref "C5") (pin "2") (pinfunction "2_2") (pintype "passive"))
      (node (ref "C6") (pin "2") (pinfunction "2_2") (pintype "passive"))
      (node (ref "C7") (pin "2") (pinfunction "2_2") (pintype "passive"))
      (node (ref "C8") (pin "2") (pinfunction "2_2") (pintype "passive"))
      (node (ref "EXT1") (pin "6") (pinfunction "6_6") (pintype "passive"))
      (node (ref "EXT2") (pin "25") (pinfunction "25_25") (pintype "passive"))
      (node (ref "EXT2") (pin "6") (pinfunction "6_6") (pintype "passive"))
      (node (ref "IC1") (pin "15") (pinfunction "G_15") (pintype "input"))
      (node (ref "IC1") (pin "8") (pinfunction "GND_8") (pintype "power_in"))
      (node (ref "IC2") (pin "15") (pinfunction "G_15") (pintype "input"))
      (node (ref "IC2") (pin "8") (pinfunction "GND_8") (pintype "power_in"))
      (node (ref "IC3") (pin "11") (pinfunction "FSYNC_11") (pintype "input"))
      (node (ref "IC3") (pin "12") (pinfunction "INT_12") (pintype "output"))
      (node (ref "IC3") (pin "18") (pinfunction "GND_18") (pintype "power_in"))
      (node (ref "IC3") (pin "20") (pinfunction "GND_20") (pintype "power_in"))
      (node (ref "R1") (pin "2") (pinfunction "2_2") (pintype "passive"))
      (node (ref "R7") (pin "1") (pinfunction "1_1") (pintype "passive"))
      (node (ref "SJ3") (pin "1") (pinfunction "1_1") (pintype "passive"))
      (node (ref "T2") (pin "2") (pinfunction "E_2") (pintype "passive"))
      (node (ref "U1") (pin "5") (pinfunction "GND_5") (pintype "passive"))
      (node (ref "U2") (pin "5") (pinfunction "GND_5") (pintype "passive"))
      (node (ref "U3") (pin "12") (pinfunction "~{G}_12") (pintype "input"))
      (node (ref "U3") (pin "8") (pinfunction "GND_8") (pintype "passive"))
      (node (ref "U4") (pin "6") (pinfunction "6_6") (pintype "passive"))
      (node (ref "U5") (pin "6") (pinfunction "6_6") (pintype "passive"))
      (node (ref "U6") (pin "6") (pinfunction "6_6") (pintype "passive"))
      (node (ref "U7") (pin "6") (pinfunction "6_6") (pintype "passive"))
      (node (ref "U8") (pin "3") (pinfunction "GND_3") (pintype "passive"))
      (node (ref "X1") (pin "8") (pinfunction "8_8") (pintype "passive"))
      (node (ref "X14") (pin "3") (pinfunction "3_3") (pintype "passive"))
      (node (ref "X14") (pin "6") (pinfunction "6_6") (pintype "passive"))
      (node (ref "X2") (pin "8") (pinfunction "8_8") (pintype "passive"))
      (node (ref "X4") (pin "4") (pinfunction "S_4") (pintype "passive"))
      (node (ref "X5") (pin "4") (pinfunction "S_4") (pintype "passive"))
      (node (ref "X6") (pin "4") (pinfunction "S_4") (pintype "passive"))
      (node (ref "X7") (pin "2") (pinfunction "S_2") (pintype "passive"))
    )
    (net (code "75") (name "GNDA") (class "Default")
      (node (ref "C10") (pin "2") (pinfunction "2_2") (pintype "passive"))
      (node (ref "C12") (pin "2") (pinfunction "2_2") (pintype "passive"))
      (node (ref "C15") (pin "2") (pinfunction "2_2") (pintype "passive"))
      (node (ref "C16") (pin "2") (pinfunction "2_2") (pintype "passive"))
      (node (ref "C17") (pin "2") (pinfunction "2_2") (pintype "passive"))
      (node (ref "C19") (pin "2") (pinfunction "2_2") (pintype "passive"))
      (node (ref "C21") (pin "2") (pinfunction "2_2") (pintype "passive"))
      (node (ref "C24") (pin "2") (pinfunction "2_2") (pintype "passive"))
      (node (ref "C25") (pin "2") (pinfunction "2_2") (pintype "passive"))
      (node (ref "C26") (pin "2") (pinfunction "2_2") (pintype "passive"))
      (node (ref "C28") (pin "2") (pinfunction "2_2") (pintype "passive"))
      (node (ref "C30") (pin "2") (pinfunction "2_2") (pintype "passive"))
      (node (ref "C33") (pin "2") (pinfunction "2_2") (pintype "passive"))
      (node (ref "C34") (pin "2") (pinfunction "2_2") (pintype "passive"))
      (node (ref "C35") (pin "2") (pinfunction "2_2") (pintype "passive"))
      (node (ref "EXT2") (pin "3") (pinfunction "3_3") (pintype "passive"))
      (node (ref "R1") (pin "1") (pinfunction "1_1") (pintype "passive"))
      (node (ref "R12") (pin "1") (pinfunction "1_1") (pintype "passive"))
      (node (ref "R23") (pin "1") (pinfunction "1_1") (pintype "passive"))
      (node (ref "R31") (pin "1") (pinfunction "1_1") (pintype "passive"))
      (node (ref "R39") (pin "1") (pinfunction "1_1") (pintype "passive"))
      (node (ref "R46") (pin "1") (pinfunction "1_1") (pintype "passive"))
      (node (ref "R51") (pin "1") (pinfunction "1_1") (pintype "passive"))
      (node (ref "U10") (pin "11") (pinfunction "VSS_11") (pintype "passive"))
      (node (ref "U11") (pin "11") (pinfunction "VSS_11") (pintype "passive"))
      (node (ref "U9") (pin "11") (pinfunction "VSS_11") (pintype "passive"))
      (node (ref "X10") (pin "2") (pinfunction "S_2") (pintype "passive"))
      (node (ref "X11") (pin "2") (pinfunction "S_2") (pintype "passive"))
      (node (ref "X12") (pin "2") (pinfunction "S_2") (pintype "passive"))
      (node (ref "X13") (pin "2") (pinfunction "S_2") (pintype "passive"))
      (node (ref "X8") (pin "2") (pinfunction "S_2") (pintype "passive"))
      (node (ref "X9") (pin "2") (pinfunction "S_2") (pintype "passive"))
    )
    (net (code "76") (name "Net-(C9-Pad1)") (class "Default")
      (node (ref "C9") (pin "1") (pinfunction "1_1") (pintype "passive"))
      (node (ref "R13") (pin "2") (pinfunction "2_2") (pintype "passive"))
      (node (ref "R14") (pin "1") (pinfunction "1_1") (pintype "passive"))
    )
    (net (code "77") (name "Net-(C11-Pad1)") (class "Default")
      (node (ref "C11") (pin "1") (pinfunction "1_1") (pintype "passive"))
      (node (ref "R15") (pin "2") (pinfunction "2_2") (pintype "passive"))
      (node (ref "R16") (pin "1") (pinfunction "1_1") (pintype "passive"))
    )
    (net (code "78") (name "Net-(C13-Pad1)") (class "Default")
      (node (ref "C13") (pin "1") (pinfunction "1_1") (pintype "passive"))
      (node (ref "R18") (pin "2") (pinfunction "2_2") (pintype "passive"))
      (node (ref "R19") (pin "1") (pinfunction "1_1") (pintype "passive"))
    )
    (net (code "79") (name "Net-(C14-Pad1)") (class "Default")
      (node (ref "C14") (pin "1") (pinfunction "1_1") (pintype "passive"))
      (node (ref "R20") (pin "2") (pinfunction "2_2") (pintype "passive"))
      (node (ref "R21") (pin "1") (pinfunction "1_1") (pintype "passive"))
    )
    (net (code "80") (name "Net-(C18-Pad1)") (class "Default")
      (node (ref "C18") (pin "1") (pinfunction "1_1") (pintype "passive"))
      (node (ref "R26") (pin "2") (pinfunction "2_2") (pintype "passive"))
      (node (ref "R27") (pin "1") (pinfunction "1_1") (pintype "passive"))
    )
    (net (code "81") (name "Net-(C20-Pad1)") (class "Default")
      (node (ref "C20") (pin "1") (pinfunction "1_1") (pintype "passive"))
      (node (ref "R29") (pin "2") (pinfunction "2_2") (pintype "passive"))
      (node (ref "R30") (pin "1") (pinfunction "1_1") (pintype "passive"))
    )
    (net (code "82") (name "Net-(C22-Pad1)") (class "Default")
      (node (ref "C22") (pin "1") (pinfunction "1_1") (pintype "passive"))
      (node (ref "R34") (pin "2") (pinfunction "2_2") (pintype "passive"))
      (node (ref "R35") (pin "1") (pinfunction "1_1") (pintype "passive"))
    )
    (net (code "83") (name "Net-(C23-Pad1)") (class "Default")
      (node (ref "C23") (pin "1") (pinfunction "1_1") (pintype "passive"))
      (node (ref "R36") (pin "2") (pinfunction "2_2") (pintype "passive"))
      (node (ref "R37") (pin "1") (pinfunction "1_1") (pintype "passive"))
    )
    (net (code "84") (name "Net-(C27-Pad1)") (class "Default")
      (node (ref "C27") (pin "1") (pinfunction "1_1") (pintype "passive"))
      (node (ref "R43") (pin "2") (pinfunction "2_2") (pintype "passive"))
      (node (ref "R44") (pin "1") (pinfunction "1_1") (pintype "passive"))
    )
    (net (code "85") (name "Net-(C29-Pad1)") (class "Default")
      (node (ref "C29") (pin "1") (pinfunction "1_1") (pintype "passive"))
      (node (ref "R47") (pin "2") (pinfunction "2_2") (pintype "passive"))
      (node (ref "R48") (pin "1") (pinfunction "1_1") (pintype "passive"))
    )
    (net (code "86") (name "Net-(C31-Pad1)") (class "Default")
      (node (ref "C31") (pin "1") (pinfunction "1_1") (pintype "passive"))
      (node (ref "R52") (pin "2") (pinfunction "2_2") (pintype "passive"))
      (node (ref "R53") (pin "1") (pinfunction "1_1") (pintype "passive"))
    )
    (net (code "87") (name "Net-(C32-Pad1)") (class "Default")
      (node (ref "C32") (pin "1") (pinfunction "1_1") (pintype "passive"))
      (node (ref "R54") (pin "2") (pinfunction "2_2") (pintype "passive"))
      (node (ref "R55") (pin "1") (pinfunction "1_1") (pintype "passive"))
    )
    (net (code "88") (name "Net-(C36-Pad1)") (class "Default")
      (node (ref "C36") (pin "1") (pinfunction "1_1") (pintype "passive"))
      (node (ref "C37") (pin "1") (pinfunction "1_1") (pintype "passive"))
      (node (ref "L1") (pin "2") (pinfunction "2_2") (pintype "passive"))
      (node (ref "X14") (pin "4") (pinfunction "4_4") (pintype "passive"))
    )
    (net (code "89") (name "Net-(IC1A-~{A}{slash}B)") (class "Default")
      (node (ref "IC1") (pin "1") (pinfunction "~{A}/B_1") (pintype "input"))
      (node (ref "IC2") (pin "1") (pinfunction "~{A}/B_1") (pintype "input"))
      (node (ref "SJ3") (pin "2") (pinfunction "2_2") (pintype "passive"))
    )
    (net (code "90") (name "Net-(IC3-REGOUT)") (class "Default")
      (node (ref "C8") (pin "1") (pinfunction "1_1") (pintype "passive"))
      (node (ref "IC3") (pin "10") (pinfunction "REGOUT_10") (pintype "input"))
    )
    (net (code "91") (name "Net-(R2-Pad2)") (class "Default")
      (node (ref "R2") (pin "2") (pinfunction "2_2") (pintype "passive"))
      (node (ref "SJ1") (pin "1") (pinfunction "1_1") (pintype "passive"))
    )
    (net (code "92") (name "Net-(R3-Pad2)") (class "Default")
      (node (ref "R3") (pin "2") (pinfunction "2_2") (pintype "passive"))
      (node (ref "SJ2") (pin "1") (pinfunction "1_1") (pintype "passive"))
    )
    (net (code "93") (name "Net-(R4-Pad1)") (class "Default")
      (node (ref "R4") (pin "1") (pinfunction "1_1") (pintype "passive"))
      (node (ref "R5") (pin "2") (pinfunction "2_2") (pintype "passive"))
      (node (ref "T1") (pin "B") (pinfunction "B_B") (pintype "passive"))
    )
    (net (code "94") (name "Net-(R10-Pad1)") (class "Default")
      (node (ref "R10") (pin "1") (pinfunction "1_1") (pintype "passive"))
      (node (ref "R11") (pin "2") (pinfunction "2_2") (pintype "passive"))
      (node (ref "R12") (pin "2") (pinfunction "2_2") (pintype "passive"))
      (node (ref "R13") (pin "1") (pinfunction "1_1") (pintype "passive"))
    )
    (net (code "95") (name "Net-(R17-Pad1)") (class "Default")
      (node (ref "R17") (pin "1") (pinfunction "1_1") (pintype "passive"))
      (node (ref "R18") (pin "1") (pinfunction "1_1") (pintype "passive"))
      (node (ref "R22") (pin "2") (pinfunction "2_2") (pintype "passive"))
      (node (ref "R23") (pin "2") (pinfunction "2_2") (pintype "passive"))
    )
    (net (code "96") (name "Net-(R24-Pad1)") (class "Default")
      (node (ref "R24") (pin "1") (pinfunction "1_1") (pintype "passive"))
      (node (ref "R25") (pin "2") (pinfunction "2_2") (pintype "passive"))
      (node (ref "R26") (pin "1") (pinfunction "1_1") (pintype "passive"))
      (node (ref "R28") (pin "2") (pinfunction "2_2") (pintype "passive"))
    )
    (net (code "97") (name "Net-(R28-Pad1)") (class "Default")
      (node (ref "R28") (pin "1") (pinfunction "1_1") (pintype "passive"))
      (node (ref "R31") (pin "2") (pinfunction "2_2") (pintype "passive"))
    )
    (net (code "98") (name "Net-(R32-Pad1)") (class "Default")
      (node (ref "R32") (pin "1") (pinfunction "1_1") (pintype "passive"))
      (node (ref "R33") (pin "2") (pinfunction "2_2") (pintype "passive"))
      (node (ref "R34") (pin "1") (pinfunction "1_1") (pintype "passive"))
      (node (ref "R38") (pin "2") (pinfunction "2_2") (pintype "passive"))
    )
    (net (code "99") (name "Net-(R38-Pad1)") (class "Default")
      (node (ref "R38") (pin "1") (pinfunction "1_1") (pintype "passive"))
      (node (ref "R39") (pin "2") (pinfunction "2_2") (pintype "passive"))
    )
    (net (code "100") (name "Net-(R40-Pad1)") (class "Default")
      (node (ref "R40") (pin "1") (pinfunction "1_1") (pintype "passive"))
      (node (ref "R41") (pin "2") (pinfunction "2_2") (pintype "passive"))
      (node (ref "R42") (pin "2") (pinfunction "2_2") (pintype "passive"))
      (node (ref "R43") (pin "1") (pinfunction "1_1") (pintype "passive"))
    )
    (net (code "101") (name "Net-(R42-Pad1)") (class "Default")
      (node (ref "R42") (pin "1") (pinfunction "1_1") (pintype "passive"))
      (node (ref "R46") (pin "2") (pinfunction "2_2") (pintype "passive"))
    )
    (net (code "102") (name "Net-(R45-Pad1)") (class "Default")
      (node (ref "R45") (pin "1") (pinfunction "1_1") (pintype "passive"))
      (node (ref "R49") (pin "2") (pinfunction "2_2") (pintype "passive"))
      (node (ref "R50") (pin "2") (pinfunction "2_2") (pintype "passive"))
      (node (ref "R52") (pin "1") (pinfunction "1_1") (pintype "passive"))
    )
    (net (code "103") (name "Net-(R50-Pad1)") (class "Default")
      (node (ref "R50") (pin "1") (pinfunction "1_1") (pintype "passive"))
      (node (ref "R51") (pin "2") (pinfunction "2_2") (pintype "passive"))
    )
    (net (code "104") (name "Net-(T2-B)") (class "Default")
      (node (ref "R6") (pin "2") (pinfunction "2_2") (pintype "passive"))
      (node (ref "R7") (pin "2") (pinfunction "2_2") (pintype "passive"))
      (node (ref "T2") (pin "1") (pinfunction "B_1") (pintype "passive"))
    )
    (net (code "105") (name "Net-(T2-C)") (class "Default")
      (node (ref "R5") (pin "1") (pinfunction "1_1") (pintype "passive"))
      (node (ref "T2") (pin "3") (pinfunction "C_3") (pintype "passive"))
    )
    (net (code "106") (name "Net-(T3-B)") (class "Default")
      (node (ref "R8") (pin "1") (pinfunction "1_1") (pintype "passive"))
      (node (ref "R9") (pin "2") (pinfunction "2_2") (pintype "passive"))
      (node (ref "T3") (pin "1") (pinfunction "B_1") (pintype "passive"))
    )
    (net (code "107") (name "Net-(U3-1A)") (class "Default")
      (node (ref "U3") (pin "2") (pinfunction "1A_2") (pintype "input"))
      (node (ref "X3") (pin "1") (pinfunction "S_1") (pintype "passive"))
    )
    (net (code "108") (name "Net-(U3-1B)") (class "Default")
      (node (ref "U3") (pin "1") (pinfunction "1B_1") (pintype "input"))
      (node (ref "X3") (pin "2") (pinfunction "S_2") (pintype "passive"))
    )
    (net (code "109") (name "Net-(U3-2A)") (class "Default")
      (node (ref "U3") (pin "6") (pinfunction "2A_6") (pintype "input"))
      (node (ref "X3") (pin "3") (pinfunction "S_3") (pintype "passive"))
    )
    (net (code "110") (name "Net-(U3-2B)") (class "Default")
      (node (ref "U3") (pin "7") (pinfunction "2B_7") (pintype "input"))
      (node (ref "X3") (pin "4") (pinfunction "S_4") (pintype "passive"))
    )
    (net (code "111") (name "Net-(U3-3A)") (class "Default")
      (node (ref "U3") (pin "10") (pinfunction "3A_10") (pintype "input"))
      (node (ref "X3") (pin "5") (pinfunction "S_5") (pintype "passive"))
    )
    (net (code "112") (name "Net-(U3-3B)") (class "Default")
      (node (ref "U3") (pin "9") (pinfunction "3B_9") (pintype "input"))
      (node (ref "X3") (pin "6") (pinfunction "S_6") (pintype "passive"))
    )
    (net (code "113") (name "Net-(U3-4A)") (class "Default")
      (node (ref "U3") (pin "14") (pinfunction "4A_14") (pintype "input"))
      (node (ref "X3") (pin "7") (pinfunction "S_7") (pintype "passive"))
    )
    (net (code "114") (name "Net-(U3-4B)") (class "Default")
      (node (ref "U3") (pin "15") (pinfunction "4B_15") (pintype "input"))
      (node (ref "X3") (pin "8") (pinfunction "S_8") (pintype "passive"))
    )
    (net (code "115") (name "Net-(U8-Y)") (class "Default")
      (node (ref "R9") (pin "1") (pinfunction "1_1") (pintype "passive"))
      (node (ref "U8") (pin "4") (pinfunction "Y_4") (pintype "output"))
    )
    (net (code "116") (name "Net-(U9-VINA+)") (class "Default")
      (node (ref "C10") (pin "1") (pinfunction "1_1") (pintype "passive"))
      (node (ref "R14") (pin "2") (pinfunction "2_2") (pintype "passive"))
      (node (ref "U9") (pin "3") (pinfunction "VINA+_3") (pintype "input"))
    )
    (net (code "117") (name "Net-(U9-VINA-)") (class "Default")
      (node (ref "C9") (pin "2") (pinfunction "2_2") (pintype "passive"))
      (node (ref "R15") (pin "1") (pinfunction "1_1") (pintype "passive"))
      (node (ref "U9") (pin "1") (pinfunction "VOUTA_1") (pintype "output"))
      (node (ref "U9") (pin "2") (pinfunction "VINA-_2") (pintype "input"))
    )
    (net (code "118") (name "Net-(U9-VINB+)") (class "Default")
      (node (ref "C12") (pin "1") (pinfunction "1_1") (pintype "passive"))
      (node (ref "R16") (pin "2") (pinfunction "2_2") (pintype "passive"))
      (node (ref "U9") (pin "5") (pinfunction "VINB+_5") (pintype "input"))
    )
    (net (code "119") (name "Net-(U9-VINC+)") (class "Default")
      (node (ref "C15") (pin "1") (pinfunction "1_1") (pintype "passive"))
      (node (ref "R19") (pin "2") (pinfunction "2_2") (pintype "passive"))
      (node (ref "U9") (pin "10") (pinfunction "VINC+_10") (pintype "input"))
    )
    (net (code "120") (name "Net-(U9-VINC-)") (class "Default")
      (node (ref "C13") (pin "2") (pinfunction "2_2") (pintype "passive"))
      (node (ref "R20") (pin "1") (pinfunction "1_1") (pintype "passive"))
      (node (ref "U9") (pin "8") (pinfunction "VOUTC_8") (pintype "output"))
      (node (ref "U9") (pin "9") (pinfunction "VINC-_9") (pintype "input"))
    )
    (net (code "121") (name "Net-(U9-VIND+)") (class "Default")
      (node (ref "C16") (pin "1") (pinfunction "1_1") (pintype "passive"))
      (node (ref "R21") (pin "2") (pinfunction "2_2") (pintype "passive"))
      (node (ref "U9") (pin "12") (pinfunction "VIND+_12") (pintype "input"))
    )
    (net (code "122") (name "Net-(U10-VINA+)") (class "Default")
      (node (ref "C19") (pin "1") (pinfunction "1_1") (pintype "passive"))
      (node (ref "R27") (pin "2") (pinfunction "2_2") (pintype "passive"))
      (node (ref "U10") (pin "3") (pinfunction "VINA+_3") (pintype "input"))
    )
    (net (code "123") (name "Net-(U10-VINA-)") (class "Default")
      (node (ref "C18") (pin "2") (pinfunction "2_2") (pintype "passive"))
      (node (ref "R29") (pin "1") (pinfunction "1_1") (pintype "passive"))
      (node (ref "U10") (pin "1") (pinfunction "VOUTA_1") (pintype "output"))
      (node (ref "U10") (pin "2") (pinfunction "VINA-_2") (pintype "input"))
    )
    (net (code "124") (name "Net-(U10-VINB+)") (class "Default")
      (node (ref "C21") (pin "1") (pinfunction "1_1") (pintype "passive"))
      (node (ref "R30") (pin "2") (pinfunction "2_2") (pintype "passive"))
      (node (ref "U10") (pin "5") (pinfunction "VINB+_5") (pintype "input"))
    )
    (net (code "125") (name "Net-(U10-VINC+)") (class "Default")
      (node (ref "C24") (pin "1") (pinfunction "1_1") (pintype "passive"))
      (node (ref "R35") (pin "2") (pinfunction "2_2") (pintype "passive"))
      (node (ref "U10") (pin "10") (pinfunction "VINC+_10") (pintype "input"))
    )
    (net (code "126") (name "Net-(U10-VINC-)") (class "Default")
      (node (ref "C22") (pin "2") (pinfunction "2_2") (pintype "passive"))
      (node (ref "R36") (pin "1") (pinfunction "1_1") (pintype "passive"))
      (node (ref "U10") (pin "8") (pinfunction "VOUTC_8") (pintype "output"))
      (node (ref "U10") (pin "9") (pinfunction "VINC-_9") (pintype "input"))
    )
    (net (code "127") (name "Net-(U10-VIND+)") (class "Default")
      (node (ref "C25") (pin "1") (pinfunction "1_1") (pintype "passive"))
      (node (ref "R37") (pin "2") (pinfunction "2_2") (pintype "passive"))
      (node (ref "U10") (pin "12") (pinfunction "VIND+_12") (pintype "input"))
    )
    (net (code "128") (name "Net-(U11-VINA+)") (class "Default")
      (node (ref "C28") (pin "1") (pinfunction "1_1") (pintype "passive"))
      (node (ref "R44") (pin "2") (pinfunction "2_2") (pintype "passive"))
      (node (ref "U11") (pin "3") (pinfunction "VINA+_3") (pintype "input"))
    )
    (net (code "129") (name "Net-(U11-VINA-)") (class "Default")
      (node (ref "C27") (pin "2") (pinfunction "2_2") (pintype "passive"))
      (node (ref "R47") (pin "1") (pinfunction "1_1") (pintype "passive"))
      (node (ref "U11") (pin "1") (pinfunction "VOUTA_1") (pintype "output"))
      (node (ref "U11") (pin "2") (pinfunction "VINA-_2") (pintype "input"))
    )
    (net (code "130") (name "Net-(U11-VINB+)") (class "Default")
      (node (ref "C30") (pin "1") (pinfunction "1_1") (pintype "passive"))
      (node (ref "R48") (pin "2") (pinfunction "2_2") (pintype "passive"))
      (node (ref "U11") (pin "5") (pinfunction "VINB+_5") (pintype "input"))
    )
    (net (code "131") (name "Net-(U11-VINC+)") (class "Default")
      (node (ref "C33") (pin "1") (pinfunction "1_1") (pintype "passive"))
      (node (ref "R53") (pin "2") (pinfunction "2_2") (pintype "passive"))
      (node (ref "U11") (pin "10") (pinfunction "VINC+_10") (pintype "input"))
    )
    (net (code "132") (name "Net-(U11-VINC-)") (class "Default")
      (node (ref "C31") (pin "2") (pinfunction "2_2") (pintype "passive"))
      (node (ref "R54") (pin "1") (pinfunction "1_1") (pintype "passive"))
      (node (ref "U11") (pin "8") (pinfunction "VOUTC_8") (pintype "output"))
      (node (ref "U11") (pin "9") (pinfunction "VINC-_9") (pintype "input"))
    )
    (net (code "133") (name "Net-(U11-VIND+)") (class "Default")
      (node (ref "C34") (pin "1") (pinfunction "1_1") (pintype "passive"))
      (node (ref "R55") (pin "2") (pinfunction "2_2") (pintype "passive"))
      (node (ref "U11") (pin "12") (pinfunction "VIND+_12") (pintype "input"))
    )
    (net (code "134") (name "Net-(X8A-S)") (class "Default")
      (node (ref "R11") (pin "1") (pinfunction "1_1") (pintype "passive"))
      (node (ref "X8") (pin "1") (pinfunction "S_1") (pintype "passive"))
    )
    (net (code "135") (name "Net-(X9A-S)") (class "Default")
      (node (ref "R22") (pin "1") (pinfunction "1_1") (pintype "passive"))
      (node (ref "X9") (pin "1") (pinfunction "S_1") (pintype "passive"))
    )
    (net (code "136") (name "Net-(X10A-S)") (class "Default")
      (node (ref "R25") (pin "1") (pinfunction "1_1") (pintype "passive"))
      (node (ref "X10") (pin "1") (pinfunction "S_1") (pintype "passive"))
    )
    (net (code "137") (name "Net-(X11A-S)") (class "Default")
      (node (ref "R33") (pin "1") (pinfunction "1_1") (pintype "passive"))
      (node (ref "X11") (pin "1") (pinfunction "S_1") (pintype "passive"))
    )
    (net (code "138") (name "Net-(X12A-S)") (class "Default")
      (node (ref "R41") (pin "1") (pinfunction "1_1") (pintype "passive"))
      (node (ref "X12") (pin "1") (pinfunction "S_1") (pintype "passive"))
    )
    (net (code "139") (name "Net-(X13A-S)") (class "Default")
      (node (ref "R49") (pin "1") (pinfunction "1_1") (pintype "passive"))
      (node (ref "X13") (pin "1") (pinfunction "S_1") (pintype "passive"))
    )
    (net (code "140") (name "unconnected-(IC2A-3A-Pad11)") (class "Default")
      (node (ref "IC2") (pin "11") (pinfunction "3A_11") (pintype "input"))
    )
    (net (code "141") (name "unconnected-(IC2A-3B-Pad10)") (class "Default")
      (node (ref "IC2") (pin "10") (pinfunction "3B_10") (pintype "input"))
    )
    (net (code "142") (name "unconnected-(IC2A-3Y-Pad9)") (class "Default")
      (node (ref "IC2") (pin "9") (pinfunction "3Y_9") (pintype "output"))
    )
    (net (code "143") (name "unconnected-(IC2A-4A-Pad14)") (class "Default")
      (node (ref "IC2") (pin "14") (pinfunction "4A_14") (pintype "input"))
    )
    (net (code "144") (name "unconnected-(IC2A-4B-Pad13)") (class "Default")
      (node (ref "IC2") (pin "13") (pinfunction "4B_13") (pintype "input"))
    )
    (net (code "145") (name "unconnected-(IC2A-4Y-Pad12)") (class "Default")
      (node (ref "IC2") (pin "12") (pinfunction "4Y_12") (pintype "output"))
    )
    (net (code "146") (name "unconnected-(IC3-AUX_CL-Pad7)") (class "Default")
      (node (ref "IC3") (pin "7") (pinfunction "AUX_CL_7") (pintype "output"))
    )
    (net (code "147") (name "unconnected-(IC3-AUX_DA-Pad21)") (class "Default")
      (node (ref "IC3") (pin "21") (pinfunction "AUX_DA_21") (pintype "bidirectional"))
    )
    (net (code "148") (name "unconnected-(U8-NC-Pad1)") (class "Default")
      (node (ref "U8") (pin "1") (pinfunction "NC_1") (pintype "no_connect"))
    )
    (net (code "149") (name "unconnected-(X1-Pad1)") (class "Default")
      (node (ref "X1") (pin "1") (pinfunction "1_1") (pintype "passive"))
    )
    (net (code "150") (name "unconnected-(X1-Pad2)") (class "Default")
      (node (ref "X1") (pin "2") (pinfunction "2_2") (pintype "passive"))
    )
    (net (code "151") (name "unconnected-(X1-Pad3)") (class "Default")
      (node (ref "X1") (pin "3") (pinfunction "3_3") (pintype "passive"))
    )
    (net (code "152") (name "unconnected-(X1-Pad6)") (class "Default")
      (node (ref "X1") (pin "6") (pinfunction "6_6") (pintype "passive"))
    )
    (net (code "153") (name "unconnected-(X1-S1-PadS@1)") (class "Default")
      (node (ref "X1") (pin "S@1") (pinfunction "S1_S@1") (pintype "passive"))
    )
    (net (code "154") (name "unconnected-(X1-S2-PadS@2)") (class "Default")
      (node (ref "X1") (pin "S@2") (pinfunction "S2_S@2") (pintype "passive"))
    )
    (net (code "155") (name "unconnected-(X2-Pad1)") (class "Default")
      (node (ref "X2") (pin "1") (pinfunction "1_1") (pintype "passive"))
    )
    (net (code "156") (name "unconnected-(X2-Pad2)") (class "Default")
      (node (ref "X2") (pin "2") (pinfunction "2_2") (pintype "passive"))
    )
    (net (code "157") (name "unconnected-(X2-Pad3)") (class "Default")
      (node (ref "X2") (pin "3") (pinfunction "3_3") (pintype "passive"))
    )
    (net (code "158") (name "unconnected-(X2-Pad6)") (class "Default")
      (node (ref "X2") (pin "6") (pinfunction "6_6") (pintype "passive"))
    )
    (net (code "159") (name "unconnected-(X2-S1-PadS@1)") (class "Default")
      (node (ref "X2") (pin "S@1") (pinfunction "S1_S@1") (pintype "passive"))
    )
    (net (code "160") (name "unconnected-(X2-S2-PadS@2)") (class "Default")
      (node (ref "X2") (pin "S@2") (pinfunction "S2_S@2") (pintype "passive"))
    )
    (net (code "161") (name "unconnected-(X14-PadSW1)") (class "Default")
      (node (ref "X14") (pin "SW1") (pinfunction "SW1_SW1") (pintype "passive"))
    )
    (net (code "162") (name "unconnected-(X14-PadSW2)") (class "Default")
      (node (ref "X14") (pin "SW2") (pinfunction "SW2_SW2") (pintype "passive"))
    )
    (net (code "163") (name "unconnected-(X14-PadSW3)") (class "Default")
      (node (ref "X14") (pin "SW3") (pinfunction "SW3_SW3") (pintype "passive"))
    )
  )
)
